# 117_05_TIMER_GATE.net
KiCad netlist of a schematic drawn in EAGLE
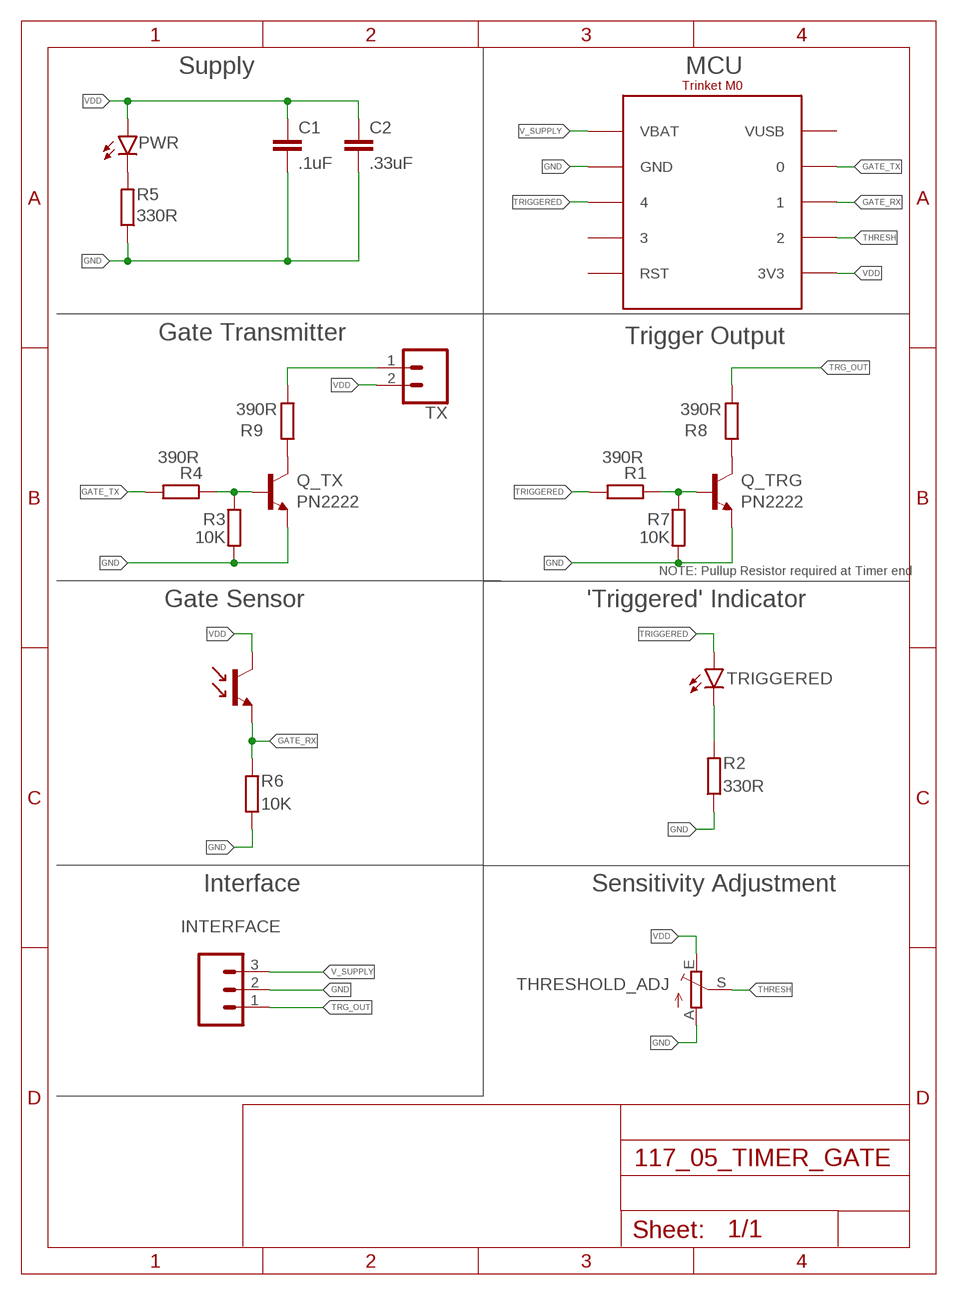
[diagram p0: schematic, sheet 1]

(export (version "E")
  (design (tool "Eeschema 10.0.6"))
  (components
    (comp (ref "C1")
      (value ".1uF")
      (footprint "eagle-import:C0805K")
      (libsource (lib "eagle-import") (part "C-EUC0805K"))
    )
    (comp (ref "C2")
      (value ".33uF")
      (footprint "eagle-import:C0805K")
      (libsource (lib "eagle-import") (part "C-EUC0805K"))
    )
    (comp (ref "INTERFACE")
      (value "CONN_03LONGPADS")
      (footprint "eagle-import:1X03_LONGPADS")
      (libsource (lib "eagle-import") (part "CONN_03LONGPADS"))
    )
    (comp (ref "PWR")
      (value "LEDSML0805")
      (footprint "eagle-import:SML0805")
      (libsource (lib "eagle-import") (part "LEDSML0805"))
    )
    (comp (ref "Q_TRG")
      (value "PN2222")
      (footprint "eagle-import:TO92-EBC")
      (libsource (lib "eagle-import") (part "-NPN-TO92-EBC2N2222"))
    )
    (comp (ref "Q_TX")
      (value "PN2222")
      (footprint "eagle-import:TO92-EBC")
      (libsource (lib "eagle-import") (part "-NPN-TO92-EBC2N2222"))
    )
    (comp (ref "R1")
      (value "390R")
      (footprint "eagle-import:M0805")
      (libsource (lib "eagle-import") (part "R-EU_M0805"))
    )
    (comp (ref "R2")
      (value "330R")
      (footprint "eagle-import:M0805")
      (libsource (lib "eagle-import") (part "R-EU_M0805"))
    )
    (comp (ref "R3")
      (value "10K")
      (footprint "eagle-import:M0805")
      (libsource (lib "eagle-import") (part "R-EU_M0805"))
    )
    (comp (ref "R4")
      (value "390R")
      (footprint "eagle-import:M0805")
      (libsource (lib "eagle-import") (part "R-EU_M0805"))
    )
    (comp (ref "R5")
      (value "330R")
      (footprint "eagle-import:M0805")
      (libsource (lib "eagle-import") (part "R-EU_M0805"))
    )
    (comp (ref "R6")
      (value "10K")
      (footprint "eagle-import:M0805")
      (libsource (lib "eagle-import") (part "R-EU_M0805"))
    )
    (comp (ref "R7")
      (value "10K")
      (footprint "eagle-import:M0805")
      (libsource (lib "eagle-import") (part "R-EU_M0805"))
    )
    (comp (ref "R8")
      (value "390R")
      (footprint "eagle-import:M0805")
      (libsource (lib "eagle-import") (part "R-EU_M0805"))
    )
    (comp (ref "R9")
      (value "390R")
      (footprint "eagle-import:M0805")
      (libsource (lib "eagle-import") (part "R-EU_M0805"))
    )
    (comp (ref "THRESHOLD_ADJ")
      (value "TRIM_EU-S64W")
      (footprint "eagle-import:S64W")
      (libsource (lib "eagle-import") (part "TRIM_EU-S64W"))
    )
    (comp (ref "TRIGGERED")
      (value "LED5MM")
      (footprint "eagle-import:LED_5MM")
      (libsource (lib "eagle-import") (part "LED5MM"))
    )
    (comp (ref "TX")
      (value "CONN_02PTH3")
      (footprint "eagle-import:1X02_LONGPADS")
      (libsource (lib "eagle-import") (part "CONN_02PTH3"))
    )
    (comp (ref "U$1")
      (value "TRINKETM0")
      (footprint "eagle-import:TRINKETM0")
      (libsource (lib "eagle-import") (part "TRINKETM0"))
    )
    (comp (ref "U$2")
      (value "PHOTOTRANSISTOR")
      (footprint "eagle-import:LED_5MM")
      (libsource (lib "eagle-import") (part "PHOTOTRANSISTOR"))
    )
  )
  (nets
    (net (code "1") (name "GATE_RX") (class "Default")
      (node (ref "R6") (pin "2") (pinfunction "2_2") (pintype "passive"))
      (node (ref "U$1") (pin "1") (pinfunction "1_1") (pintype "bidirectional"))
      (node (ref "U$2") (pin "K") (pinfunction "E_K") (pintype "passive"))
    )
    (net (code "2") (name "GATE_TX") (class "Default")
      (node (ref "R4") (pin "2") (pinfunction "2_2") (pintype "passive"))
      (node (ref "U$1") (pin "0") (pinfunction "0_0") (pintype "bidirectional"))
    )
    (net (code "3") (name "GND") (class "Default")
      (node (ref "C1") (pin "2") (pinfunction "2_2") (pintype "passive"))
      (node (ref "C2") (pin "2") (pinfunction "2_2") (pintype "passive"))
      (node (ref "INTERFACE") (pin "2") (pinfunction "2_2") (pintype "passive"))
      (node (ref "Q_TRG") (pin "E") (pinfunction "E_E") (pintype "passive"))
      (node (ref "Q_TX") (pin "E") (pinfunction "E_E") (pintype "passive"))
      (node (ref "R2") (pin "1") (pinfunction "1_1") (pintype "passive"))
      (node (ref "R3") (pin "2") (pinfunction "2_2") (pintype "passive"))
      (node (ref "R5") (pin "1") (pinfunction "1_1") (pintype "passive"))
      (node (ref "R6") (pin "1") (pinfunction "1_1") (pintype "passive"))
      (node (ref "R7") (pin "2") (pinfunction "2_2") (pintype "passive"))
      (node (ref "THRESHOLD_ADJ") (pin "A") (pinfunction "A_A") (pintype "passive"))
      (node (ref "U$1") (pin "GND") (pinfunction "GND_GND") (pintype "bidirectional"))
    )
    (net (code "4") (name "Net-(PWR-PadC)") (class "Default")
      (node (ref "PWR") (pin "C") (pinfunction "C_C") (pintype "passive"))
      (node (ref "R5") (pin "2") (pinfunction "2_2") (pintype "passive"))
    )
    (net (code "5") (name "Net-(Q_TRG-PadB)") (class "Default")
      (node (ref "Q_TRG") (pin "B") (pinfunction "B_B") (pintype "passive"))
      (node (ref "R1") (pin "1") (pinfunction "1_1") (pintype "passive"))
      (node (ref "R7") (pin "1") (pinfunction "1_1") (pintype "passive"))
    )
    (net (code "6") (name "Net-(Q_TRG-PadC)") (class "Default")
      (node (ref "Q_TRG") (pin "C") (pinfunction "C_C") (pintype "passive"))
      (node (ref "R8") (pin "2") (pinfunction "2_2") (pintype "passive"))
    )
    (net (code "7") (name "Net-(Q_TX-PadB)") (class "Default")
      (node (ref "Q_TX") (pin "B") (pinfunction "B_B") (pintype "passive"))
      (node (ref "R3") (pin "1") (pinfunction "1_1") (pintype "passive"))
      (node (ref "R4") (pin "1") (pinfunction "1_1") (pintype "passive"))
    )
    (net (code "8") (name "Net-(Q_TX-PadC)") (class "Default")
      (node (ref "Q_TX") (pin "C") (pinfunction "C_C") (pintype "passive"))
      (node (ref "R9") (pin "2") (pinfunction "2_2") (pintype "passive"))
    )
    (net (code "9") (name "Net-(R9-Pad1)") (class "Default")
      (node (ref "R9") (pin "1") (pinfunction "1_1") (pintype "passive"))
      (node (ref "TX") (pin "1") (pinfunction "1_1") (pintype "passive"))
    )
    (net (code "10") (name "Net-(TRIGGERED-C)") (class "Default")
      (node (ref "R2") (pin "2") (pinfunction "2_2") (pintype "passive"))
      (node (ref "TRIGGERED") (pin "K") (pinfunction "C_K") (pintype "passive"))
    )
    (net (code "11") (name "THRESH") (class "Default")
      (node (ref "THRESHOLD_ADJ") (pin "S") (pinfunction "S_S") (pintype "passive"))
      (node (ref "U$1") (pin "2") (pinfunction "2_2") (pintype "bidirectional"))
    )
    (net (code "12") (name "TRG_OUT") (class "Default")
      (node (ref "INTERFACE") (pin "1") (pinfunction "1_1") (pintype "passive"))
      (node (ref "R8") (pin "1") (pinfunction "1_1") (pintype "passive"))
    )
    (net (code "13") (name "TRIGGERED") (class "Default")
      (node (ref "R1") (pin "2") (pinfunction "2_2") (pintype "passive"))
      (node (ref "TRIGGERED") (pin "A") (pinfunction "A_A") (pintype "passive"))
      (node (ref "U$1") (pin "4") (pinfunction "4_4") (pintype "bidirectional"))
    )
    (net (code "14") (name "VDD") (class "Default")
      (node (ref "C1") (pin "1") (pinfunction "1_1") (pintype "passive"))
      (node (ref "C2") (pin "1") (pinfunction "1_1") (pintype "passive"))
      (node (ref "PWR") (pin "A") (pinfunction "A_A") (pintype "passive"))
      (node (ref "THRESHOLD_ADJ") (pin "E") (pinfunction "E_E") (pintype "passive"))
      (node (ref "TX") (pin "2") (pinfunction "2_2") (pintype "passive"))
      (node (ref "U$1") (pin "3V3") (pinfunction "3V3_3V3") (pintype "bidirectional"))
      (node (ref "U$2") (pin "A") (pinfunction "C_A") (pintype "passive"))
    )
    (net (code "15") (name "V_SUPPLY") (class "Default")
      (node (ref "INTERFACE") (pin "3") (pinfunction "3_3") (pintype "passive"))
      (node (ref "U$1") (pin "VBAT") (pinfunction "VBAT_VBAT") (pintype "bidirectional"))
    )
    (net (code "16") (name "unconnected-(U$1-Pad3)") (class "Default")
      (node (ref "U$1") (pin "3") (pinfunction "3_3") (pintype "bidirectional"))
    )
    (net (code "17") (name "unconnected-(U$1-PadRST)") (class "Default")
      (node (ref "U$1") (pin "RST") (pinfunction "RST_RST") (pintype "bidirectional"))
    )
    (net (code "18") (name "unconnected-(U$1-PadVUSB)") (class "Default")
      (node (ref "U$1") (pin "VUSB") (pinfunction "VUSB_VUSB") (pintype "bidirectional"))
    )
  )
)
